# watCalSchematic.net
KiCad netlist of a schematic drawn in EAGLE
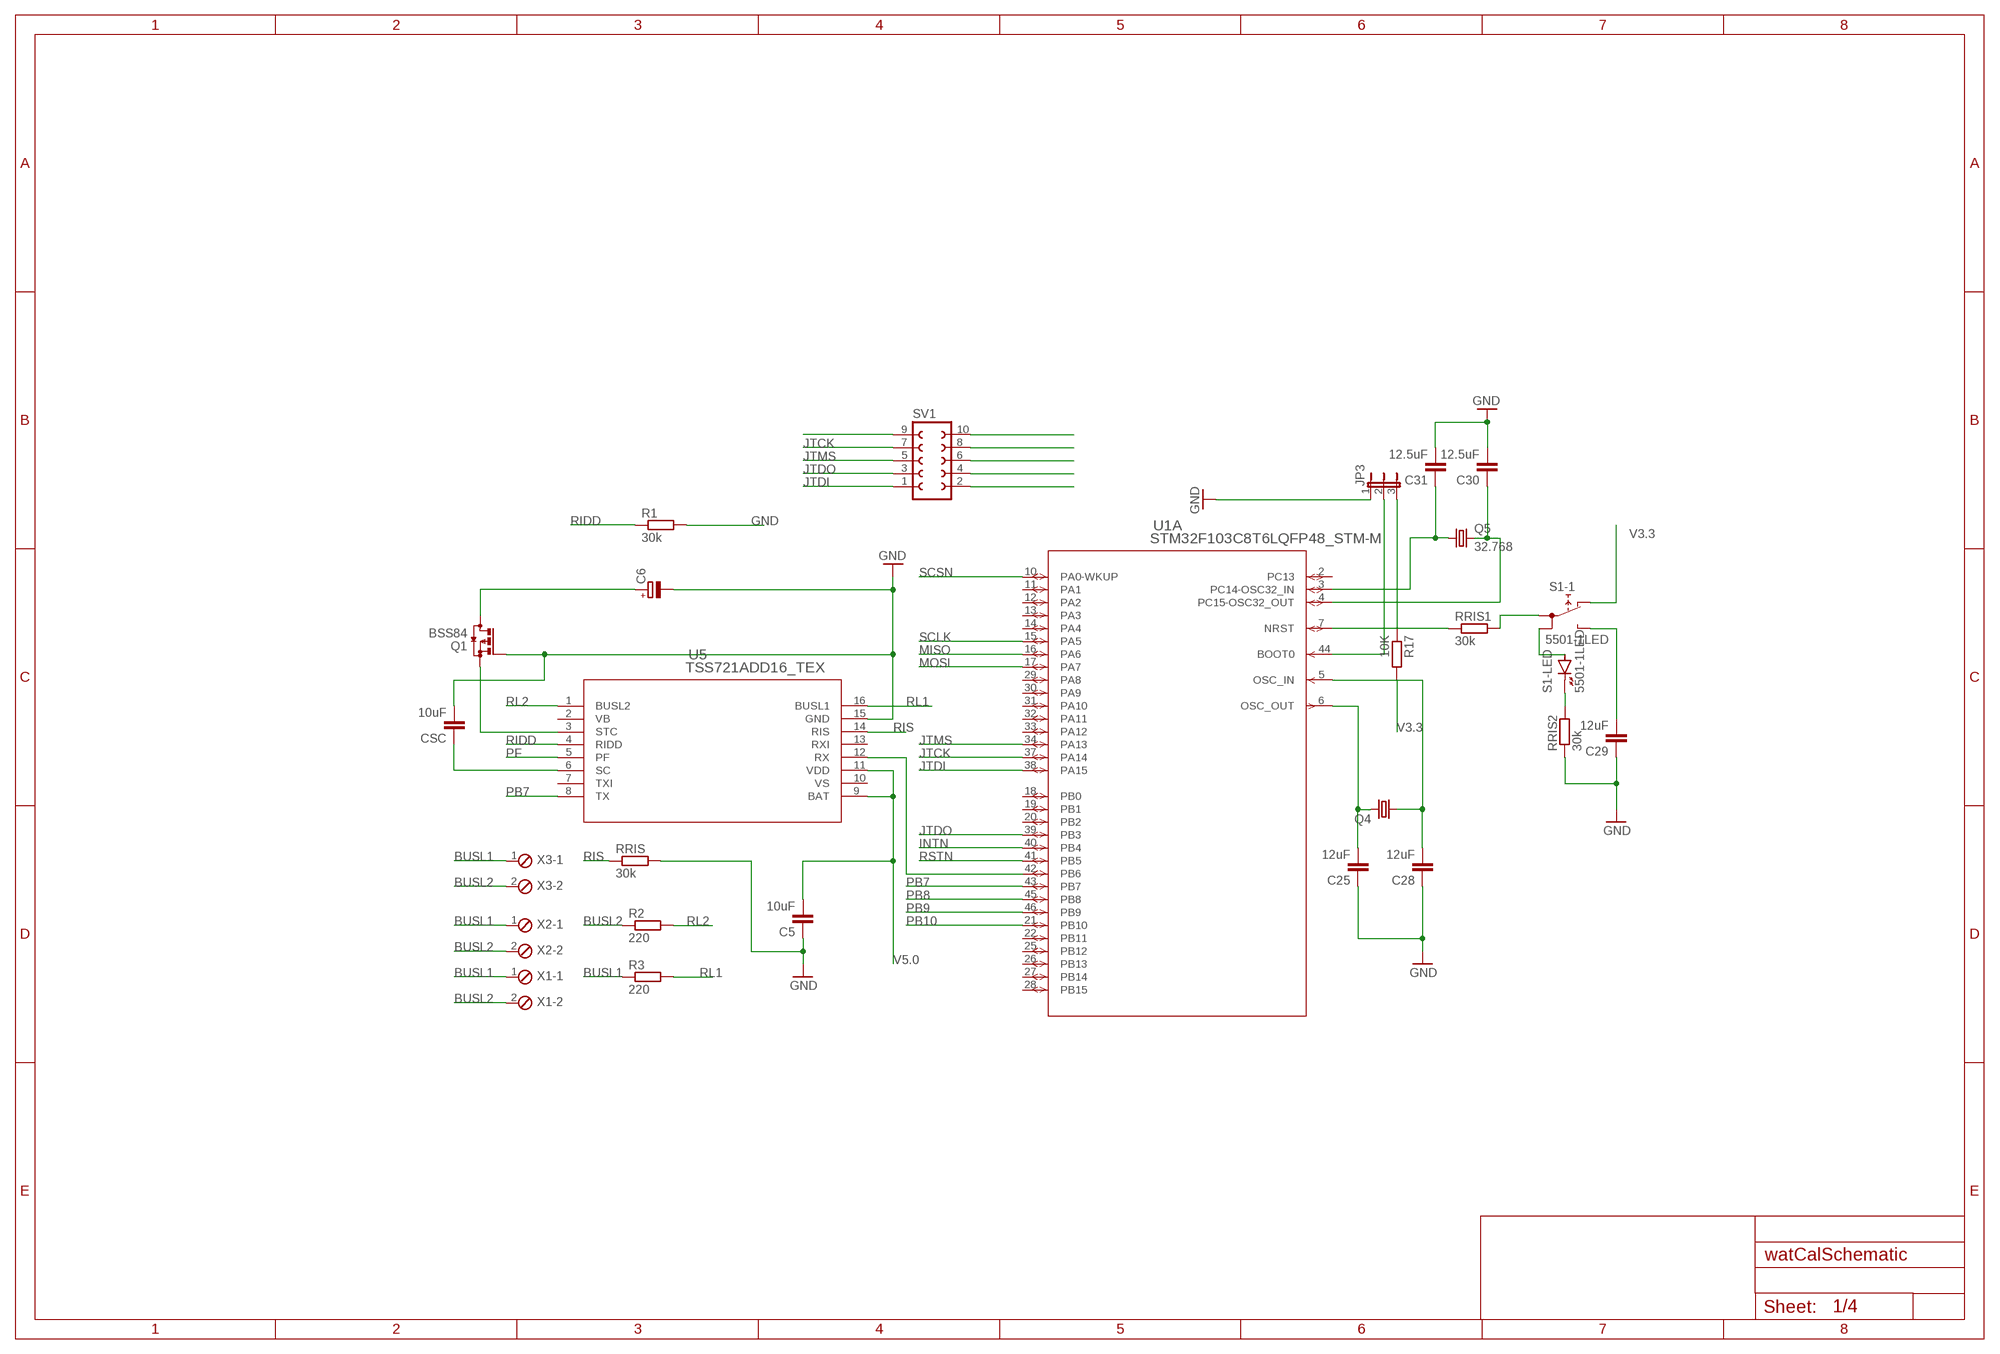
[diagram p0: schematic, sheet 1]
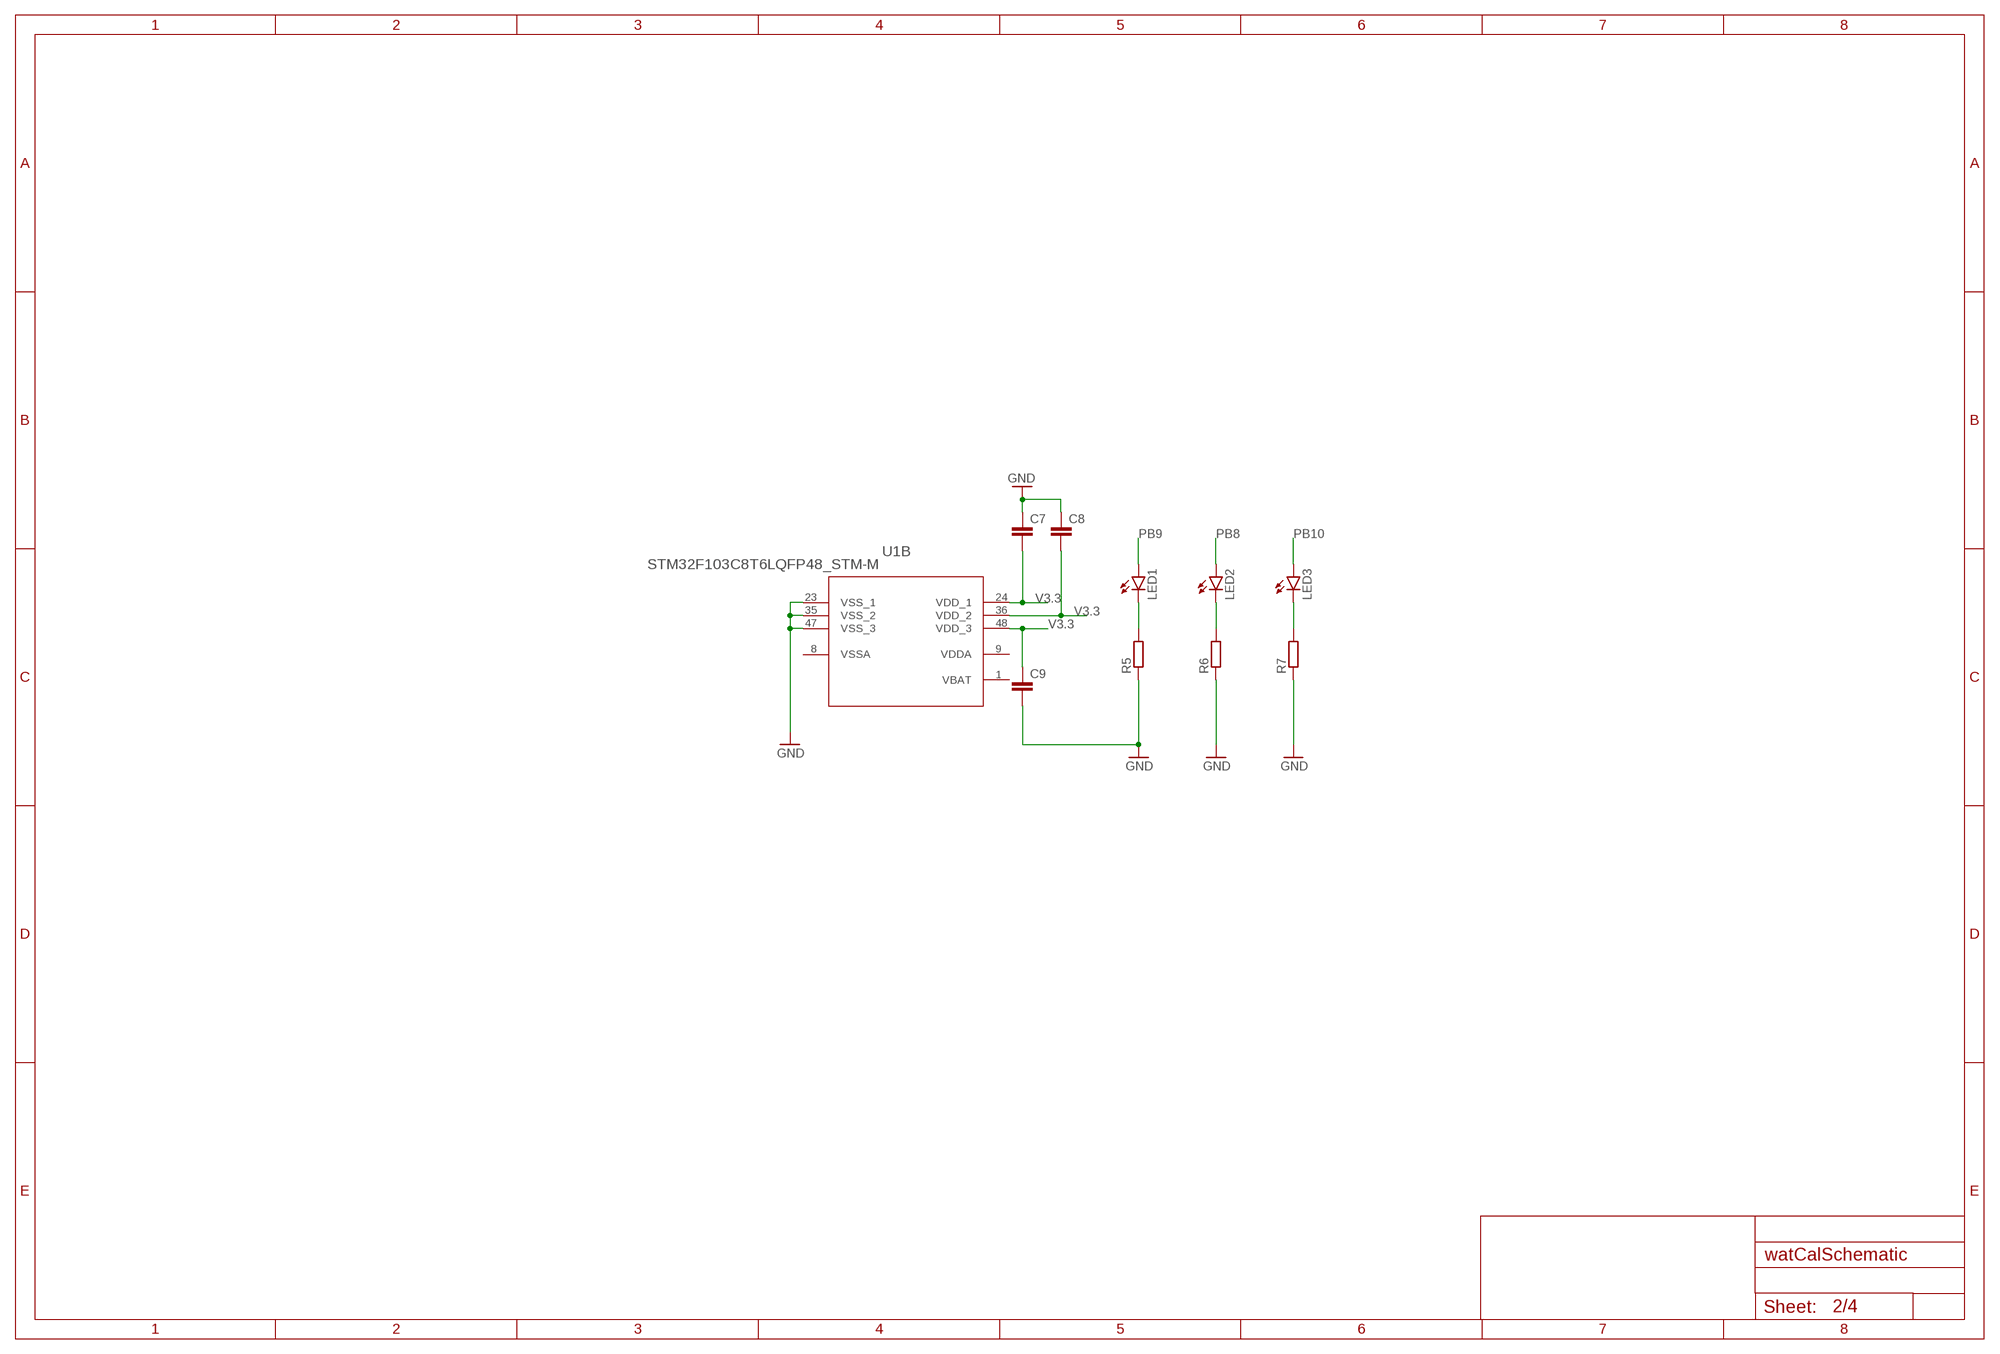
[diagram p1: schematic, sheet 2]
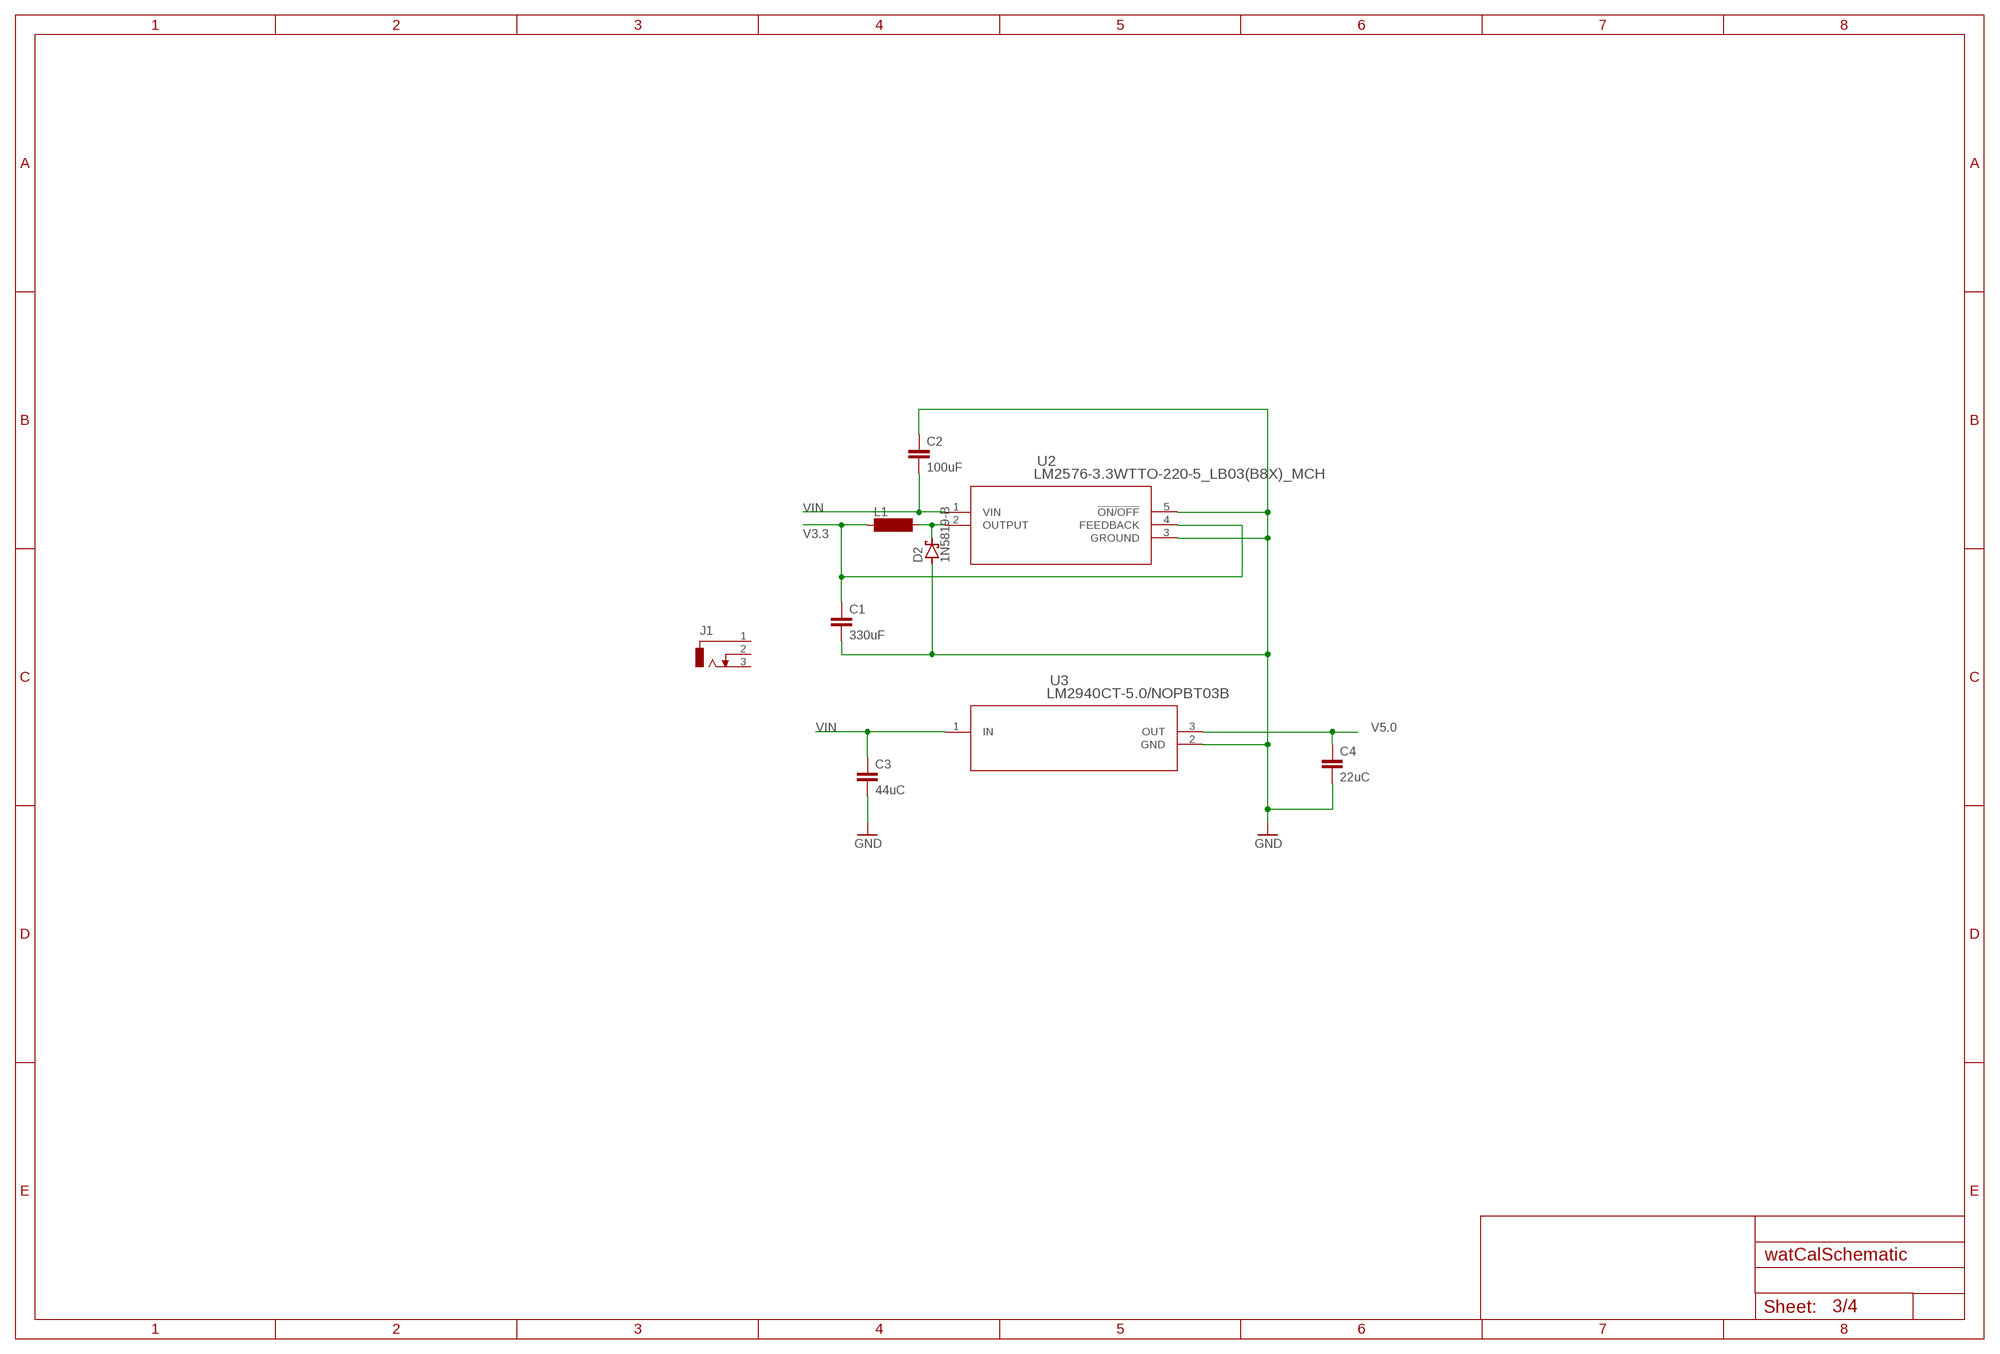
[diagram p2: schematic, sheet 3]
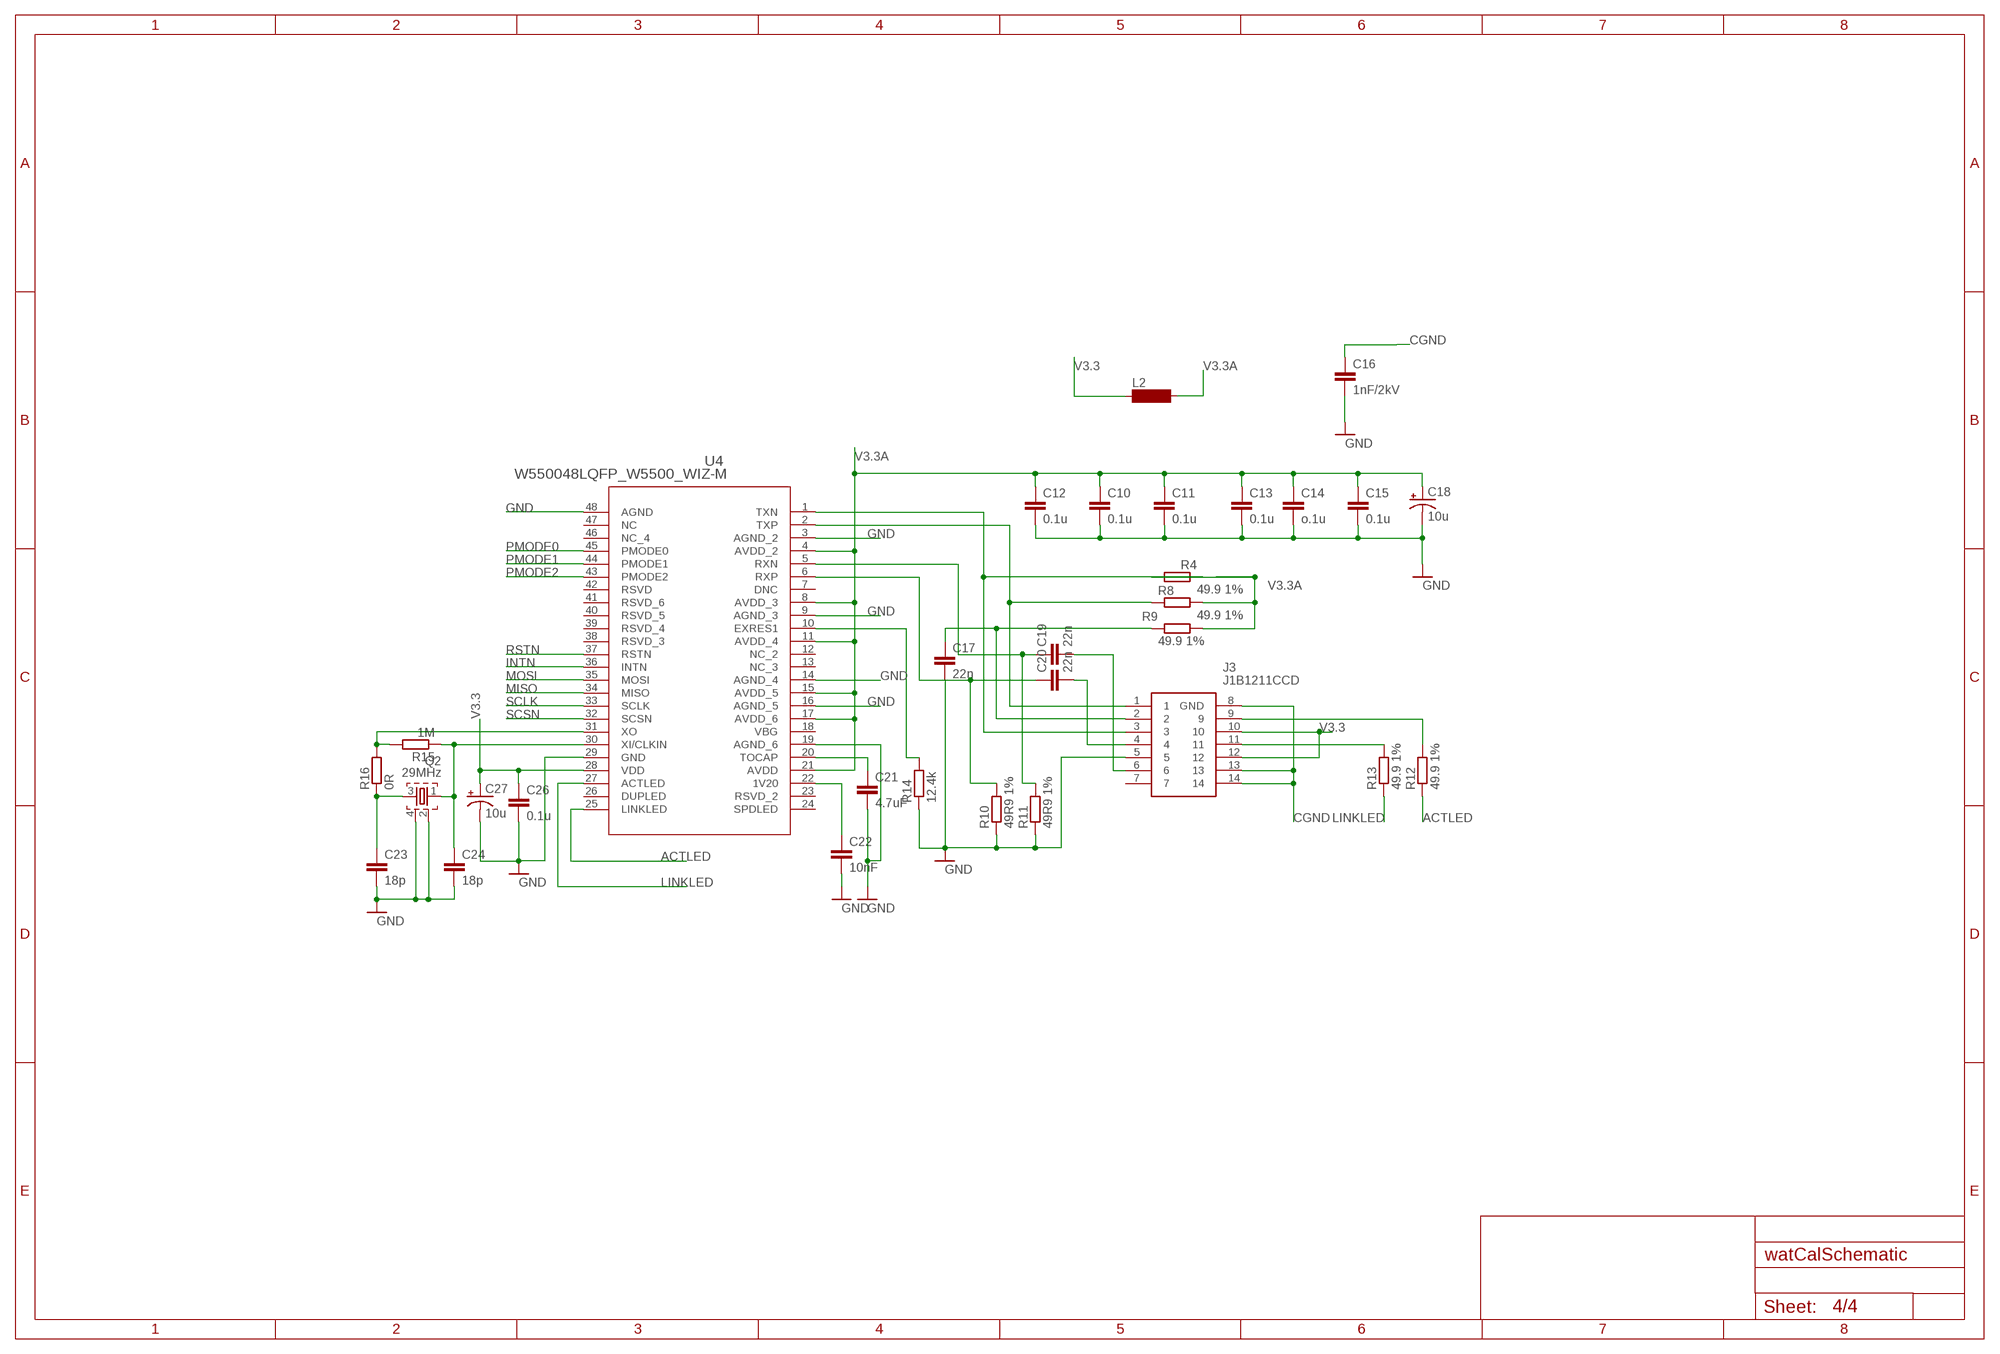
[diagram p3: schematic, sheet 4]

(export (version "E")
  (design (tool "Eeschema 10.0.6"))
  (components
    (comp (ref "C1")
      (value "330uF")
      (footprint "eagle-import:C2.5-2")
      (libsource (lib "eagle-import") (part "C2.5/2"))
    )
    (comp (ref "C2")
      (value "100uF")
      (footprint "eagle-import:C2.5-2")
      (libsource (lib "eagle-import") (part "C2.5/2"))
    )
    (comp (ref "C3")
      (value "44uC")
      (footprint "eagle-import:C2.5-3")
      (libsource (lib "eagle-import") (part "C2,5-3"))
    )
    (comp (ref "C4")
      (value "22uC")
      (footprint "eagle-import:C2.5-3")
      (libsource (lib "eagle-import") (part "C2,5-3"))
    )
    (comp (ref "D2")
      (value "1N5819-B")
      (footprint "eagle-import:DO41-7.6")
      (libsource (lib "eagle-import") (part "1N5819-B"))
    )
    (comp (ref "J1")
      (value "DCJ0303")
      (footprint "eagle-import:DCJ0303")
      (libsource (lib "eagle-import") (part "DCJ0303"))
    )
    (comp (ref "L1")
      (value "SD8")
      (footprint "eagle-import:SD8")
      (libsource (lib "eagle-import") (part "SD8"))
    )
    (comp (ref "U2")
      (value "LM2576-3.3WTTO-220-5_LB03(B8X)_MCH")
      (footprint "eagle-import:TO-220-5_LB03(B8X)_MCH")
      (fields
        (field (name "MANUFACTURER_PART_NUMBER") "LM2576-3.3WT")
        (field (name "COPYRIGHT") "Copyright (C) 2024 Ultra Librarian. All rights reserved.")
      )
      (libsource (lib "eagle-import") (part "LM2576-3.3WTTO-220-5_LB03(B8X)_MCH"))
    )
    (comp (ref "U3")
      (value "LM2940CT-5.0/NOPBT03B")
      (footprint "eagle-import:T03B")
      (fields
        (field (name "MANUFACTURER_PART_NUMBER") "LM2940CT-5.0/NOPB")
        (field (name "COPYRIGHT") "Copyright (C) 2024 Ultra Librarian. All rights reserved.")
      )
      (libsource (lib "eagle-import") (part "LM2940CT-5.0/NOPBT03B"))
    )
    (comp (ref "C7")
      (value "C2.5/2")
      (footprint "eagle-import:C2.5-2")
      (libsource (lib "eagle-import") (part "C2.5/2"))
    )
    (comp (ref "C8")
      (value "C2.5/2")
      (footprint "eagle-import:C2.5-2")
      (libsource (lib "eagle-import") (part "C2.5/2"))
    )
    (comp (ref "C9")
      (value "C2.5/2")
      (footprint "eagle-import:C2.5-2")
      (libsource (lib "eagle-import") (part "C2.5/2"))
    )
    (comp (ref "LED1")
      (value "LED5MM")
      (footprint "eagle-import:LED5MM")
      (libsource (lib "eagle-import") (part "LED5MM"))
    )
    (comp (ref "LED2")
      (value "LED5MM")
      (footprint "eagle-import:LED5MM")
      (libsource (lib "eagle-import") (part "LED5MM"))
    )
    (comp (ref "LED3")
      (value "LED5MM")
      (footprint "eagle-import:LED5MM")
      (libsource (lib "eagle-import") (part "LED5MM"))
    )
    (comp (ref "R5")
      (value "R-EU_0207/10")
      (footprint "eagle-import:0207_10")
      (libsource (lib "eagle-import") (part "R-EU_0207/10"))
    )
    (comp (ref "R6")
      (value "R-EU_0207/10")
      (footprint "eagle-import:0207_10")
      (libsource (lib "eagle-import") (part "R-EU_0207/10"))
    )
    (comp (ref "R7")
      (value "R-EU_0207/10")
      (footprint "eagle-import:0207_10")
      (libsource (lib "eagle-import") (part "R-EU_0207/10"))
    )
    (comp (ref "U1")
      (value "STM32F103C8T6LQFP48_STM-M")
      (footprint "eagle-import:LQFP48_STM-M")
      (fields
        (field (name "MANUFACTURER_PART_NUMBER") "STM32F103C8T6")
        (field (name "COPYRIGHT") "Copyright (C) 2024 Ultra Librarian. All rights reserved.")
      )
      (libsource (lib "eagle-import") (part "STM32F103C8T6LQFP48_STM-M"))
    )
    (comp (ref "C5")
      (value "10uF")
      (footprint "eagle-import:C2.5-2")
      (libsource (lib "eagle-import") (part "C2.5/2"))
    )
    (comp (ref "C6")
      (value "CPOL-EUE2,5-6E")
      (footprint "eagle-import:E2,5-6E")
      (libsource (lib "eagle-import") (part "CPOL-EUE2,5-6E"))
    )
    (comp (ref "C25")
      (value "12uF")
      (footprint "eagle-import:C2.5-2")
      (libsource (lib "eagle-import") (part "C2.5/2"))
    )
    (comp (ref "C28")
      (value "12uF")
      (footprint "eagle-import:C2.5-2")
      (libsource (lib "eagle-import") (part "C2.5/2"))
    )
    (comp (ref "C29")
      (value "12uF")
      (footprint "eagle-import:C2.5-2")
      (libsource (lib "eagle-import") (part "C2.5/2"))
    )
    (comp (ref "C30")
      (value "12.5uF")
      (footprint "eagle-import:C2.5-2")
      (libsource (lib "eagle-import") (part "C2.5/2"))
    )
    (comp (ref "C31")
      (value "12.5uF")
      (footprint "eagle-import:C2.5-2")
      (libsource (lib "eagle-import") (part "C2.5/2"))
    )
    (comp (ref "CSC")
      (value "10uF")
      (footprint "eagle-import:C2.5-2")
      (libsource (lib "eagle-import") (part "C2.5/2"))
    )
    (comp (ref "JP3")
      (value "JP2E")
      (footprint "eagle-import:JP2")
      (libsource (lib "eagle-import") (part "JP2E"))
    )
    (comp (ref "Q1")
      (value "BSS84")
      (footprint "eagle-import:SOT23")
      (libsource (lib "eagle-import") (part "BSS84"))
    )
    (comp (ref "Q4")
      (value "CRYSTALHC49S")
      (footprint "eagle-import:HC49_S")
      (libsource (lib "eagle-import") (part "CRYSTALHC49S"))
    )
    (comp (ref "Q5")
      (value "32.768")
      (footprint "eagle-import:FC-12M")
      (libsource (lib "eagle-import") (part "FC-12M"))
    )
    (comp (ref "R1")
      (value "30k")
      (footprint "eagle-import:0207_10")
      (libsource (lib "eagle-import") (part "R-EU_0207/10"))
    )
    (comp (ref "R2")
      (value "220")
      (footprint "eagle-import:0207_10")
      (libsource (lib "eagle-import") (part "R-EU_0207/10"))
    )
    (comp (ref "R3")
      (value "220")
      (footprint "eagle-import:0207_10")
      (libsource (lib "eagle-import") (part "R-EU_0207/10"))
    )
    (comp (ref "R17")
      (value "10K")
      (footprint "eagle-import:0207_10")
      (libsource (lib "eagle-import") (part "R-EU_0207/10"))
    )
    (comp (ref "RRIS")
      (value "30k")
      (footprint "eagle-import:0207_10")
      (libsource (lib "eagle-import") (part "R-EU_0207/10"))
    )
    (comp (ref "RRIS1")
      (value "30k")
      (footprint "eagle-import:0207_10")
      (libsource (lib "eagle-import") (part "R-EU_0207/10"))
    )
    (comp (ref "RRIS2")
      (value "30k")
      (footprint "eagle-import:0207_10")
      (libsource (lib "eagle-import") (part "R-EU_0207/10"))
    )
    (comp (ref "S1")
      (value "5501-1LED")
      (footprint "eagle-import:5501-1LED")
      (libsource (lib "eagle-import") (part "55?-1LED01"))
    )
    (comp (ref "SV1")
      (value "FE05-2")
      (footprint "eagle-import:FE05-2")
      (libsource (lib "eagle-import") (part "FE05-2"))
    )
    (comp (ref "U5")
      (value "TSS721ADD16_TEX")
      (footprint "eagle-import:D16_TEX")
      (fields
        (field (name "MANUFACTURER_PART_NUMBER") "TSS721AD")
        (field (name "COPYRIGHT") "Copyright (C) 2024 Ultra Librarian. All rights reserved.")
      )
      (libsource (lib "eagle-import") (part "TSS721ADD16_TEX"))
    )
    (comp (ref "X1")
      (value "MPT2")
      (footprint "eagle-import:2POL254")
      (libsource (lib "eagle-import") (part "MPT2"))
    )
    (comp (ref "X2")
      (value "MPT2")
      (footprint "eagle-import:2POL254")
      (libsource (lib "eagle-import") (part "MPT2"))
    )
    (comp (ref "X3")
      (value "MPT2")
      (footprint "eagle-import:2POL254")
      (libsource (lib "eagle-import") (part "MPT2"))
    )
    (comp (ref "C10")
      (value "0.1u")
      (footprint "eagle-import:C2.5-2")
      (libsource (lib "eagle-import") (part "C2.5/2"))
    )
    (comp (ref "C11")
      (value "0.1u")
      (footprint "eagle-import:C2.5-2")
      (libsource (lib "eagle-import") (part "C2.5/2"))
    )
    (comp (ref "C12")
      (value "0.1u")
      (footprint "eagle-import:C2.5-2")
      (libsource (lib "eagle-import") (part "C2.5/2"))
    )
    (comp (ref "C13")
      (value "0.1u")
      (footprint "eagle-import:C2.5-2")
      (libsource (lib "eagle-import") (part "C2.5/2"))
    )
    (comp (ref "C14")
      (value "o.1u")
      (footprint "eagle-import:C2.5-2")
      (libsource (lib "eagle-import") (part "C2.5/2"))
    )
    (comp (ref "C15")
      (value "0.1u")
      (footprint "eagle-import:C2.5-2")
      (libsource (lib "eagle-import") (part "C2.5/2"))
    )
    (comp (ref "C16")
      (value "1nF/2kV")
      (footprint "eagle-import:C2.5-2")
      (libsource (lib "eagle-import") (part "C2.5/2"))
    )
    (comp (ref "C17")
      (value "22n")
      (footprint "eagle-import:C2.5-2")
      (libsource (lib "eagle-import") (part "C2.5/2"))
    )
    (comp (ref "C18")
      (value "10u")
      (footprint "eagle-import:E2,5-6")
      (libsource (lib "eagle-import") (part "CPOL-USE2.5-6"))
    )
    (comp (ref "C19")
      (value "22n")
      (footprint "eagle-import:C2.5-2")
      (libsource (lib "eagle-import") (part "C2.5/2"))
    )
    (comp (ref "C20")
      (value "22n")
      (footprint "eagle-import:C2.5-2")
      (libsource (lib "eagle-import") (part "C2.5/2"))
    )
    (comp (ref "C21")
      (value "4.7uF")
      (footprint "eagle-import:C2.5-2")
      (libsource (lib "eagle-import") (part "C2.5/2"))
    )
    (comp (ref "C22")
      (value "10nF")
      (footprint "eagle-import:C2.5-2")
      (libsource (lib "eagle-import") (part "C2.5/2"))
    )
    (comp (ref "C23")
      (value "18p")
      (footprint "eagle-import:C2.5-2")
      (libsource (lib "eagle-import") (part "C2.5/2"))
    )
    (comp (ref "C24")
      (value "18p")
      (footprint "eagle-import:C2.5-2")
      (libsource (lib "eagle-import") (part "C2.5/2"))
    )
    (comp (ref "C26")
      (value "0.1u")
      (footprint "eagle-import:C2.5-2")
      (libsource (lib "eagle-import") (part "C2.5/2"))
    )
    (comp (ref "C27")
      (value "10u")
      (footprint "eagle-import:E2,5-6")
      (libsource (lib "eagle-import") (part "CPOL-USE2.5-6"))
    )
    (comp (ref "J3")
      (value "J1B1211CCD")
      (footprint "eagle-import:J1B1211CCD")
      (libsource (lib "eagle-import") (part "J1B1211CCD"))
    )
    (comp (ref "L2")
      (value "SD8")
      (footprint "eagle-import:SD8")
      (libsource (lib "eagle-import") (part "SD8"))
    )
    (comp (ref "Q2")
      (value "29MHz")
      (footprint "eagle-import:FA-20H")
      (libsource (lib "eagle-import") (part "FA-20H"))
    )
    (comp (ref "R4")
      (value "49.9 1%")
      (footprint "eagle-import:0207_10")
      (libsource (lib "eagle-import") (part "R-EU_0207/10"))
    )
    (comp (ref "R8")
      (value "49.9 1%")
      (footprint "eagle-import:0207_10")
      (libsource (lib "eagle-import") (part "R-EU_0207/10"))
    )
    (comp (ref "R9")
      (value "49.9 1%")
      (footprint "eagle-import:0207_10")
      (libsource (lib "eagle-import") (part "R-EU_0207/10"))
    )
    (comp (ref "R10")
      (value "49R9 1%")
      (footprint "eagle-import:0207_10")
      (libsource (lib "eagle-import") (part "R-EU_0207/10"))
    )
    (comp (ref "R11")
      (value "49R9 1%")
      (footprint "eagle-import:0207_10")
      (libsource (lib "eagle-import") (part "R-EU_0207/10"))
    )
    (comp (ref "R12")
      (value "49.9 1%")
      (footprint "eagle-import:0207_10")
      (libsource (lib "eagle-import") (part "R-EU_0207/10"))
    )
    (comp (ref "R13")
      (value "49.9 1%")
      (footprint "eagle-import:0207_10")
      (libsource (lib "eagle-import") (part "R-EU_0207/10"))
    )
    (comp (ref "R14")
      (value "12.4k")
      (footprint "eagle-import:0207_10")
      (libsource (lib "eagle-import") (part "R-EU_0207/10"))
    )
    (comp (ref "R15")
      (value "1M")
      (footprint "eagle-import:0207_10")
      (libsource (lib "eagle-import") (part "R-EU_0207/10"))
    )
    (comp (ref "R16")
      (value "0R")
      (footprint "eagle-import:0207_10")
      (libsource (lib "eagle-import") (part "R-EU_0207/10"))
    )
    (comp (ref "U4")
      (value "W550048LQFP_W5500_WIZ-M")
      (footprint "eagle-import:48LQFP_W5500_WIZ-M")
      (fields
        (field (name "MANUFACTURER_PART_NUMBER") "W5500")
        (field (name "COPYRIGHT") "Copyright (C) 2024 Ultra Librarian. All rights reserved.")
      )
      (libsource (lib "eagle-import") (part "W550048LQFP_W5500_WIZ-M"))
    )
  )
  (nets
    (net (code "1") (name "ACTLED") (class "Default")
      (node (ref "R12") (pin "1") (pinfunction "1_1") (pintype "passive"))
      (node (ref "U4") (pin "25") (pinfunction "LINKLED_25") (pintype "passive"))
    )
    (net (code "2") (name "BUSL1") (class "Default")
      (node (ref "R3") (pin "1") (pinfunction "1_1") (pintype "passive"))
      (node (ref "X1") (pin "1") (pinfunction "1_1") (pintype "passive"))
      (node (ref "X2") (pin "1") (pinfunction "1_1") (pintype "passive"))
      (node (ref "X3") (pin "1") (pinfunction "1_1") (pintype "passive"))
    )
    (net (code "3") (name "BUSL2") (class "Default")
      (node (ref "R2") (pin "1") (pinfunction "1_1") (pintype "passive"))
      (node (ref "X1") (pin "2") (pinfunction "1_2") (pintype "passive"))
      (node (ref "X2") (pin "2") (pinfunction "1_2") (pintype "passive"))
      (node (ref "X3") (pin "2") (pinfunction "1_2") (pintype "passive"))
    )
    (net (code "4") (name "CGND") (class "Default")
      (node (ref "C16") (pin "1") (pinfunction "1_1") (pintype "passive"))
      (node (ref "J3") (pin "13") (pinfunction "13_13") (pintype "bidirectional"))
      (node (ref "J3") (pin "14") (pinfunction "14_14") (pintype "bidirectional"))
      (node (ref "J3") (pin "8") (pinfunction "GND_8") (pintype "bidirectional"))
    )
    (net (code "5") (name "GND") (class "Default")
      (node (ref "C1") (pin "2") (pinfunction "2_2") (pintype "passive"))
      (node (ref "C10") (pin "2") (pinfunction "2_2") (pintype "passive"))
      (node (ref "C11") (pin "2") (pinfunction "2_2") (pintype "passive"))
      (node (ref "C12") (pin "2") (pinfunction "2_2") (pintype "passive"))
      (node (ref "C13") (pin "2") (pinfunction "2_2") (pintype "passive"))
      (node (ref "C14") (pin "2") (pinfunction "2_2") (pintype "passive"))
      (node (ref "C15") (pin "2") (pinfunction "2_2") (pintype "passive"))
      (node (ref "C16") (pin "2") (pinfunction "2_2") (pintype "passive"))
      (node (ref "C17") (pin "2") (pinfunction "2_2") (pintype "passive"))
      (node (ref "C18") (pin "-") (pinfunction "-_-") (pintype "passive"))
      (node (ref "C2") (pin "1") (pinfunction "1_1") (pintype "passive"))
      (node (ref "C21") (pin "2") (pinfunction "2_2") (pintype "passive"))
      (node (ref "C22") (pin "2") (pinfunction "2_2") (pintype "passive"))
      (node (ref "C23") (pin "2") (pinfunction "2_2") (pintype "passive"))
      (node (ref "C24") (pin "2") (pinfunction "2_2") (pintype "passive"))
      (node (ref "C25") (pin "1") (pinfunction "1_1") (pintype "passive"))
      (node (ref "C26") (pin "2") (pinfunction "2_2") (pintype "passive"))
      (node (ref "C27") (pin "-") (pinfunction "-_-") (pintype "passive"))
      (node (ref "C28") (pin "1") (pinfunction "1_1") (pintype "passive"))
      (node (ref "C29") (pin "1") (pinfunction "1_1") (pintype "passive"))
      (node (ref "C3") (pin "2") (pinfunction "2_2") (pintype "passive"))
      (node (ref "C30") (pin "2") (pinfunction "2_2") (pintype "passive"))
      (node (ref "C31") (pin "2") (pinfunction "2_2") (pintype "passive"))
      (node (ref "C4") (pin "2") (pinfunction "2_2") (pintype "passive"))
      (node (ref "C5") (pin "1") (pinfunction "1_1") (pintype "passive"))
      (node (ref "C6") (pin "-") (pinfunction "-_-") (pintype "passive"))
      (node (ref "C7") (pin "1") (pinfunction "1_1") (pintype "passive"))
      (node (ref "C8") (pin "1") (pinfunction "1_1") (pintype "passive"))
      (node (ref "C9") (pin "2") (pinfunction "2_2") (pintype "passive"))
      (node (ref "CSC") (pin "2") (pinfunction "2_2") (pintype "passive"))
      (node (ref "D2") (pin "A") (pinfunction "A_A") (pintype "passive"))
      (node (ref "J3") (pin "5") (pinfunction "5_5") (pintype "bidirectional"))
      (node (ref "JP3") (pin "1") (pinfunction "1_1") (pintype "passive"))
      (node (ref "Q1") (pin "1") (pinfunction "G_1") (pintype "passive"))
      (node (ref "Q2") (pin "2") (pinfunction "2_2") (pintype "passive"))
      (node (ref "Q2") (pin "4") (pinfunction "4_4") (pintype "passive"))
      (node (ref "R1") (pin "2") (pinfunction "2_2") (pintype "passive"))
      (node (ref "R10") (pin "1") (pinfunction "1_1") (pintype "passive"))
      (node (ref "R11") (pin "1") (pinfunction "1_1") (pintype "passive"))
      (node (ref "R14") (pin "1") (pinfunction "1_1") (pintype "passive"))
      (node (ref "R5") (pin "1") (pinfunction "1_1") (pintype "passive"))
      (node (ref "R6") (pin "1") (pinfunction "1_1") (pintype "passive"))
      (node (ref "R7") (pin "1") (pinfunction "1_1") (pintype "passive"))
      (node (ref "RRIS") (pin "2") (pinfunction "2_2") (pintype "passive"))
      (node (ref "RRIS2") (pin "1") (pinfunction "1_1") (pintype "passive"))
      (node (ref "U1") (pin "23") (pinfunction "VSS_1_23") (pintype "power_in"))
      (node (ref "U1") (pin "35") (pinfunction "VSS_2_35") (pintype "power_in"))
      (node (ref "U1") (pin "47") (pinfunction "VSS_3_47") (pintype "power_in"))
      (node (ref "U2") (pin "3") (pinfunction "GROUND_3") (pintype "passive"))
      (node (ref "U2") (pin "5") (pinfunction "~{ON/OFF}_5") (pintype "input"))
      (node (ref "U3") (pin "2") (pinfunction "GND_2") (pintype "passive"))
      (node (ref "U4") (pin "14") (pinfunction "AGND_4_14") (pintype "passive"))
      (node (ref "U4") (pin "16") (pinfunction "AGND_5_16") (pintype "passive"))
      (node (ref "U4") (pin "19") (pinfunction "AGND_6_19") (pintype "passive"))
      (node (ref "U4") (pin "29") (pinfunction "GND_29") (pintype "passive"))
      (node (ref "U4") (pin "3") (pinfunction "AGND_2_3") (pintype "passive"))
      (node (ref "U4") (pin "48") (pinfunction "AGND_48") (pintype "passive"))
      (node (ref "U4") (pin "9") (pinfunction "AGND_3_9") (pintype "passive"))
      (node (ref "U5") (pin "15") (pinfunction "GND_15") (pintype "power_in"))
    )
    (net (code "6") (name "INTN") (class "Default")
      (node (ref "U1") (pin "40") (pinfunction "PB4_40") (pintype "bidirectional"))
      (node (ref "U4") (pin "36") (pinfunction "INTN_36") (pintype "passive"))
    )
    (net (code "7") (name "JTCK") (class "Default")
      (node (ref "SV1") (pin "7") (pinfunction "7_7") (pintype "passive"))
      (node (ref "U1") (pin "37") (pinfunction "PA14_37") (pintype "bidirectional"))
    )
    (net (code "8") (name "JTDI") (class "Default")
      (node (ref "SV1") (pin "1") (pinfunction "1_1") (pintype "passive"))
      (node (ref "U1") (pin "38") (pinfunction "PA15_38") (pintype "bidirectional"))
    )
    (net (code "9") (name "JTDO") (class "Default")
      (node (ref "SV1") (pin "3") (pinfunction "3_3") (pintype "passive"))
      (node (ref "U1") (pin "39") (pinfunction "PB3_39") (pintype "bidirectional"))
    )
    (net (code "10") (name "JTMS") (class "Default")
      (node (ref "SV1") (pin "5") (pinfunction "5_5") (pintype "passive"))
      (node (ref "U1") (pin "34") (pinfunction "PA13_34") (pintype "bidirectional"))
    )
    (net (code "11") (name "LINKLED") (class "Default")
      (node (ref "R13") (pin "1") (pinfunction "1_1") (pintype "passive"))
      (node (ref "U4") (pin "27") (pinfunction "ACTLED_27") (pintype "passive"))
    )
    (net (code "12") (name "MISO") (class "Default")
      (node (ref "U1") (pin "16") (pinfunction "PA6_16") (pintype "bidirectional"))
      (node (ref "U4") (pin "34") (pinfunction "MISO_34") (pintype "passive"))
    )
    (net (code "13") (name "MOSI") (class "Default")
      (node (ref "U1") (pin "17") (pinfunction "PA7_17") (pintype "bidirectional"))
      (node (ref "U4") (pin "35") (pinfunction "MOSI_35") (pintype "passive"))
    )
    (net (code "14") (name "Net-(C17-Pad1)") (class "Default")
      (node (ref "C17") (pin "1") (pinfunction "1_1") (pintype "passive"))
      (node (ref "J3") (pin "2") (pinfunction "2_2") (pintype "bidirectional"))
      (node (ref "R9") (pin "1") (pinfunction "1_1") (pintype "passive"))
    )
    (net (code "15") (name "Net-(C19-Pad2)") (class "Default")
      (node (ref "C19") (pin "2") (pinfunction "2_2") (pintype "passive"))
      (node (ref "J3") (pin "6") (pinfunction "6_6") (pintype "bidirectional"))
    )
    (net (code "16") (name "Net-(C20-Pad2)") (class "Default")
      (node (ref "C20") (pin "2") (pinfunction "2_2") (pintype "passive"))
      (node (ref "J3") (pin "4") (pinfunction "4_4") (pintype "bidirectional"))
    )
    (net (code "17") (name "Net-(C23-Pad1)") (class "Default")
      (node (ref "C23") (pin "1") (pinfunction "1_1") (pintype "passive"))
      (node (ref "Q2") (pin "3") (pinfunction "3_3") (pintype "passive"))
      (node (ref "R16") (pin "1") (pinfunction "1_1") (pintype "passive"))
    )
    (net (code "18") (name "Net-(C29-Pad2)") (class "Default")
      (node (ref "C29") (pin "2") (pinfunction "2_2") (pintype "passive"))
      (node (ref "S1") (pin "NO") (pinfunction "NO_NO") (pintype "passive"))
    )
    (net (code "19") (name "Net-(J3-Pad9)") (class "Default")
      (node (ref "J3") (pin "9") (pinfunction "9_9") (pintype "bidirectional"))
      (node (ref "R12") (pin "2") (pinfunction "2_2") (pintype "passive"))
    )
    (net (code "20") (name "Net-(J3-Pad11)") (class "Default")
      (node (ref "J3") (pin "11") (pinfunction "11_11") (pintype "bidirectional"))
      (node (ref "R13") (pin "2") (pinfunction "2_2") (pintype "passive"))
    )
    (net (code "21") (name "Net-(JP3-Pad3)") (class "Default")
      (node (ref "JP3") (pin "3") (pinfunction "3_3") (pintype "passive"))
      (node (ref "R17") (pin "1") (pinfunction "1_1") (pintype "passive"))
    )
    (net (code "22") (name "Net-(LED1-C)") (class "Default")
      (node (ref "LED1") (pin "K") (pinfunction "C_K") (pintype "passive"))
      (node (ref "R5") (pin "2") (pinfunction "2_2") (pintype "passive"))
    )
    (net (code "23") (name "Net-(LED2-C)") (class "Default")
      (node (ref "LED2") (pin "K") (pinfunction "C_K") (pintype "passive"))
      (node (ref "R6") (pin "2") (pinfunction "2_2") (pintype "passive"))
    )
    (net (code "24") (name "Net-(LED3-C)") (class "Default")
      (node (ref "LED3") (pin "K") (pinfunction "C_K") (pintype "passive"))
      (node (ref "R7") (pin "2") (pinfunction "2_2") (pintype "passive"))
    )
    (net (code "25") (name "Net-(Q1-D)") (class "Default")
      (node (ref "C6") (pin "+") (pinfunction "+_+") (pintype "passive"))
      (node (ref "Q1") (pin "3") (pinfunction "D_3") (pintype "passive"))
    )
    (net (code "26") (name "Net-(Q1-S)") (class "Default")
      (node (ref "Q1") (pin "2") (pinfunction "S_2") (pintype "passive"))
      (node (ref "U5") (pin "3") (pinfunction "STC_3") (pintype "passive"))
    )
    (net (code "27") (name "Net-(RRIS1-Pad2)") (class "Default")
      (node (ref "RRIS1") (pin "2") (pinfunction "2_2") (pintype "passive"))
      (node (ref "S1") (pin "1A") (pinfunction "1A_1A") (pintype "passive"))
    )
    (net (code "28") (name "Net-(S1B-A)") (class "Default")
      (node (ref "S1") (pin "+") (pinfunction "A_+") (pintype "passive"))
      (node (ref "S1") (pin "1B") (pinfunction "1B_1B") (pintype "passive"))
    )
    (net (code "29") (name "Net-(S1B-K)") (class "Default")
      (node (ref "RRIS2") (pin "2") (pinfunction "2_2") (pintype "passive"))
      (node (ref "S1") (pin "-") (pinfunction "K_-") (pintype "passive"))
    )
    (net (code "30") (name "Net-(U1A-BOOT0)") (class "Default")
      (node (ref "JP3") (pin "2") (pinfunction "2_2") (pintype "passive"))
      (node (ref "U1") (pin "44") (pinfunction "BOOT0_44") (pintype "input"))
    )
    (net (code "31") (name "Net-(U1A-NRST)") (class "Default")
      (node (ref "RRIS1") (pin "1") (pinfunction "1_1") (pintype "passive"))
      (node (ref "U1") (pin "7") (pinfunction "NRST_7") (pintype "bidirectional"))
    )
    (net (code "32") (name "Net-(U1A-OSC_IN)") (class "Default")
      (node (ref "C28") (pin "2") (pinfunction "2_2") (pintype "passive"))
      (node (ref "Q4") (pin "1") (pinfunction "1_1") (pintype "passive"))
      (node (ref "U1") (pin "5") (pinfunction "OSC_IN_5") (pintype "input"))
    )
    (net (code "33") (name "Net-(U1A-OSC_OUT)") (class "Default")
      (node (ref "C25") (pin "2") (pinfunction "2_2") (pintype "passive"))
      (node (ref "Q4") (pin "2") (pinfunction "2_2") (pintype "passive"))
      (node (ref "U1") (pin "6") (pinfunction "OSC_OUT_6") (pintype "output"))
    )
    (net (code "34") (name "Net-(U1A-PB6)") (class "Default")
      (node (ref "U1") (pin "42") (pinfunction "PB6_42") (pintype "bidirectional"))
      (node (ref "U5") (pin "12") (pinfunction "RX_12") (pintype "input"))
    )
    (net (code "35") (name "Net-(U1A-PC14-OSC32_IN)") (class "Default")
      (node (ref "C31") (pin "1") (pinfunction "1_1") (pintype "passive"))
      (node (ref "Q5") (pin "1") (pinfunction "1_1") (pintype "passive"))
      (node (ref "U1") (pin "3") (pinfunction "PC14-OSC32_IN_3") (pintype "bidirectional"))
    )
    (net (code "36") (name "Net-(U1A-PC15-OSC32_OUT)") (class "Default")
      (node (ref "C30") (pin "1") (pinfunction "1_1") (pintype "passive"))
      (node (ref "Q5") (pin "2") (pinfunction "2_2") (pintype "passive"))
      (node (ref "U1") (pin "4") (pinfunction "PC15-OSC32_OUT_4") (pintype "bidirectional"))
    )
    (net (code "37") (name "Net-(U2-OUTPUT)") (class "Default")
      (node (ref "D2") (pin "C") (pinfunction "C_C") (pintype "passive"))
      (node (ref "L1") (pin "2") (pinfunction "2_2") (pintype "passive"))
      (node (ref "U2") (pin "2") (pinfunction "OUTPUT_2") (pintype "output"))
    )
    (net (code "38") (name "Net-(U4-1V20)") (class "Default")
      (node (ref "C22") (pin "1") (pinfunction "1_1") (pintype "passive"))
      (node (ref "U4") (pin "22") (pinfunction "1V20_22") (pintype "passive"))
    )
    (net (code "39") (name "Net-(U4-EXRES1)") (class "Default")
      (node (ref "R14") (pin "2") (pinfunction "2_2") (pintype "passive"))
      (node (ref "U4") (pin "10") (pinfunction "EXRES1_10") (pintype "passive"))
    )
    (net (code "40") (name "Net-(U4-RXN)") (class "Default")
      (node (ref "C19") (pin "1") (pinfunction "1_1") (pintype "passive"))
      (node (ref "R11") (pin "2") (pinfunction "2_2") (pintype "passive"))
      (node (ref "U4") (pin "5") (pinfunction "RXN_5") (pintype "passive"))
    )
    (net (code "41") (name "Net-(U4-RXP)") (class "Default")
      (node (ref "C20") (pin "1") (pinfunction "1_1") (pintype "passive"))
      (node (ref "R10") (pin "2") (pinfunction "2_2") (pintype "passive"))
      (node (ref "U4") (pin "6") (pinfunction "RXP_6") (pintype "passive"))
    )
    (net (code "42") (name "Net-(U4-TOCAP)") (class "Default")
      (node (ref "C21") (pin "1") (pinfunction "1_1") (pintype "passive"))
      (node (ref "U4") (pin "20") (pinfunction "TOCAP_20") (pintype "passive"))
    )
    (net (code "43") (name "Net-(U4-TXN)") (class "Default")
      (node (ref "J3") (pin "3") (pinfunction "3_3") (pintype "bidirectional"))
      (node (ref "R4") (pin "1") (pinfunction "1_1") (pintype "passive"))
      (node (ref "U4") (pin "1") (pinfunction "TXN_1") (pintype "passive"))
    )
    (net (code "44") (name "Net-(U4-TXP)") (class "Default")
      (node (ref "J3") (pin "1") (pinfunction "1_1") (pintype "bidirectional"))
      (node (ref "R8") (pin "1") (pinfunction "1_1") (pintype "passive"))
      (node (ref "U4") (pin "2") (pinfunction "TXP_2") (pintype "passive"))
    )
    (net (code "45") (name "Net-(U4-XI{slash}CLKIN)") (class "Default")
      (node (ref "C24") (pin "1") (pinfunction "1_1") (pintype "passive"))
      (node (ref "Q2") (pin "1") (pinfunction "1_1") (pintype "passive"))
      (node (ref "R15") (pin "1") (pinfunction "1_1") (pintype "passive"))
      (node (ref "U4") (pin "30") (pinfunction "XI/CLKIN_30") (pintype "passive"))
    )
    (net (code "46") (name "Net-(U5-SC)") (class "Default")
      (node (ref "CSC") (pin "1") (pinfunction "1_1") (pintype "passive"))
      (node (ref "U5") (pin "6") (pinfunction "SC_6") (pintype "passive"))
    )
    (net (code "47") (name "PB7") (class "Default")
      (node (ref "U1") (pin "43") (pinfunction "PB7_43") (pintype "bidirectional"))
      (node (ref "U5") (pin "8") (pinfunction "TX_8") (pintype "output"))
    )
    (net (code "48") (name "PB8") (class "Default")
      (node (ref "LED2") (pin "A") (pinfunction "A_A") (pintype "passive"))
      (node (ref "U1") (pin "45") (pinfunction "PB8_45") (pintype "bidirectional"))
    )
    (net (code "49") (name "PB9") (class "Default")
      (node (ref "LED1") (pin "A") (pinfunction "A_A") (pintype "passive"))
      (node (ref "U1") (pin "46") (pinfunction "PB9_46") (pintype "bidirectional"))
    )
    (net (code "50") (name "PB10") (class "Default")
      (node (ref "LED3") (pin "A") (pinfunction "A_A") (pintype "passive"))
      (node (ref "U1") (pin "21") (pinfunction "PB10_21") (pintype "bidirectional"))
    )
    (net (code "51") (name "PF") (class "Default")
      (node (ref "U5") (pin "5") (pinfunction "PF_5") (pintype "output"))
    )
    (net (code "52") (name "PMODE0") (class "Default")
      (node (ref "U4") (pin "45") (pinfunction "PMODE0_45") (pintype "bidirectional"))
    )
    (net (code "53") (name "PMODE1") (class "Default")
      (node (ref "U4") (pin "44") (pinfunction "PMODE1_44") (pintype "bidirectional"))
    )
    (net (code "54") (name "PMODE2") (class "Default")
      (node (ref "U4") (pin "43") (pinfunction "PMODE2_43") (pintype "bidirectional"))
    )
    (net (code "55") (name "RIDD") (class "Default")
      (node (ref "R1") (pin "1") (pinfunction "1_1") (pintype "passive"))
      (node (ref "U5") (pin "4") (pinfunction "RIDD_4") (pintype "input"))
    )
    (net (code "56") (name "RIS") (class "Default")
      (node (ref "RRIS") (pin "1") (pinfunction "1_1") (pintype "passive"))
      (node (ref "U5") (pin "14") (pinfunction "RIS_14") (pintype "input"))
    )
    (net (code "57") (name "RL1") (class "Default")
      (node (ref "R3") (pin "2") (pinfunction "2_2") (pintype "passive"))
      (node (ref "U5") (pin "16") (pinfunction "BUSL1_16") (pintype "passive"))
    )
    (net (code "58") (name "RL2") (class "Default")
      (node (ref "R2") (pin "2") (pinfunction "2_2") (pintype "passive"))
      (node (ref "U5") (pin "1") (pinfunction "BUSL2_1") (pintype "passive"))
    )
    (net (code "59") (name "RSTN") (class "Default")
      (node (ref "U1") (pin "41") (pinfunction "PB5_41") (pintype "bidirectional"))
      (node (ref "U4") (pin "37") (pinfunction "RSTN_37") (pintype "passive"))
    )
    (net (code "60") (name "SCLK") (class "Default")
      (node (ref "U1") (pin "15") (pinfunction "PA5_15") (pintype "bidirectional"))
      (node (ref "U4") (pin "33") (pinfunction "SCLK_33") (pintype "passive"))
    )
    (net (code "61") (name "SCSN") (class "Default")
      (node (ref "R15") (pin "2") (pinfunction "2_2") (pintype "passive"))
      (node (ref "R16") (pin "2") (pinfunction "2_2") (pintype "passive"))
      (node (ref "U1") (pin "10") (pinfunction "PA0-WKUP_10") (pintype "bidirectional"))
      (node (ref "U4") (pin "31") (pinfunction "XO_31") (pintype "passive"))
    )
    (net (code "62") (name "V3.3") (class "Default")
      (node (ref "C1") (pin "1") (pinfunction "1_1") (pintype "passive"))
      (node (ref "C26") (pin "1") (pinfunction "1_1") (pintype "passive"))
      (node (ref "C27") (pin "+") (pinfunction "+_+") (pintype "passive"))
      (node (ref "C7") (pin "2") (pinfunction "2_2") (pintype "passive"))
      (node (ref "C8") (pin "2") (pinfunction "2_2") (pintype "passive"))
      (node (ref "C9") (pin "1") (pinfunction "1_1") (pintype "passive"))
      (node (ref "J3") (pin "10") (pinfunction "10_10") (pintype "bidirectional"))
      (node (ref "J3") (pin "12") (pinfunction "12_12") (pintype "bidirectional"))
      (node (ref "L1") (pin "1") (pinfunction "1_1") (pintype "passive"))
      (node (ref "L2") (pin "1") (pinfunction "1_1") (pintype "passive"))
      (node (ref "R17") (pin "2") (pinfunction "2_2") (pintype "passive"))
      (node (ref "S1") (pin "NC") (pinfunction "NC_NC") (pintype "passive"))
      (node (ref "U1") (pin "24") (pinfunction "VDD_1_24") (pintype "power_in"))
      (node (ref "U1") (pin "36") (pinfunction "VDD_2_36") (pintype "power_in"))
      (node (ref "U1") (pin "48") (pinfunction "VDD_3_48") (pintype "power_in"))
      (node (ref "U2") (pin "4") (pinfunction "FEEDBACK_4") (pintype "output"))
      (node (ref "U4") (pin "28") (pinfunction "VDD_28") (pintype "power_in"))
    )
    (net (code "63") (name "V3.3A") (class "Default")
      (node (ref "C10") (pin "1") (pinfunction "1_1") (pintype "passive"))
      (node (ref "C11") (pin "1") (pinfunction "1_1") (pintype "passive"))
      (node (ref "C12") (pin "1") (pinfunction "1_1") (pintype "passive"))
      (node (ref "C13") (pin "1") (pinfunction "1_1") (pintype "passive"))
      (node (ref "C14") (pin "1") (pinfunction "1_1") (pintype "passive"))
      (node (ref "C15") (pin "1") (pinfunction "1_1") (pintype "passive"))
      (node (ref "C18") (pin "+") (pinfunction "+_+") (pintype "passive"))
      (node (ref "L2") (pin "2") (pinfunction "2_2") (pintype "passive"))
      (node (ref "R4") (pin "2") (pinfunction "2_2") (pintype "passive"))
      (node (ref "R8") (pin "2") (pinfunction "2_2") (pintype "passive"))
      (node (ref "R9") (pin "2") (pinfunction "2_2") (pintype "passive"))
      (node (ref "U4") (pin "11") (pinfunction "AVDD_4_11") (pintype "power_in"))
      (node (ref "U4") (pin "15") (pinfunction "AVDD_5_15") (pintype "power_in"))
      (node (ref "U4") (pin "17") (pinfunction "AVDD_6_17") (pintype "power_in"))
      (node (ref "U4") (pin "21") (pinfunction "AVDD_21") (pintype "power_in"))
      (node (ref "U4") (pin "4") (pinfunction "AVDD_2_4") (pintype "power_in"))
      (node (ref "U4") (pin "8") (pinfunction "AVDD_3_8") (pintype "power_in"))
    )
    (net (code "64") (name "V5.0") (class "Default")
      (node (ref "C4") (pin "1") (pinfunction "1_1") (pintype "passive"))
      (node (ref "C5") (pin "2") (pinfunction "2_2") (pintype "passive"))
      (node (ref "U3") (pin "3") (pinfunction "OUT_3") (pintype "output"))
      (node (ref "U5") (pin "11") (pinfunction "VDD_11") (pintype "power_in"))
      (node (ref "U5") (pin "9") (pinfunction "BAT_9") (pintype "passive"))
    )
    (net (code "65") (name "VBAT") (class "Default")
      (node (ref "U1") (pin "1") (pinfunction "VBAT_1") (pintype "power_in"))
    )
    (net (code "66") (name "VDDA") (class "Default")
      (node (ref "U1") (pin "9") (pinfunction "VDDA_9") (pintype "power_in"))
    )
    (net (code "67") (name "VIN") (class "Default")
      (node (ref "C2") (pin "2") (pinfunction "2_2") (pintype "passive"))
      (node (ref "C3") (pin "1") (pinfunction "1_1") (pintype "passive"))
      (node (ref "U2") (pin "1") (pinfunction "VIN_1") (pintype "power_in"))
      (node (ref "U3") (pin "1") (pinfunction "IN_1") (pintype "input"))
    )
    (net (code "68") (name "VSSA") (class "Default")
      (node (ref "U1") (pin "8") (pinfunction "VSSA_8") (pintype "power_in"))
    )
    (net (code "69") (name "unconnected-(J1-Pad1)") (class "Default")
      (node (ref "J1") (pin "1") (pinfunction "1_1") (pintype "passive"))
    )
    (net (code "70") (name "unconnected-(J1-Pad2)") (class "Default")
      (node (ref "J1") (pin "2") (pinfunction "2_2") (pintype "passive"))
    )
    (net (code "71") (name "unconnected-(J1-Pad3)") (class "Default")
      (node (ref "J1") (pin "3") (pinfunction "3_3") (pintype "passive"))
    )
    (net (code "72") (name "unconnected-(J3-Pad7)") (class "Default")
      (node (ref "J3") (pin "7") (pinfunction "7_7") (pintype "bidirectional"))
    )
    (net (code "73") (name "unconnected-(SV1-Pad2)") (class "Default")
      (node (ref "SV1") (pin "2") (pinfunction "2_2") (pintype "passive"))
    )
    (net (code "74") (name "unconnected-(SV1-Pad4)") (class "Default")
      (node (ref "SV1") (pin "4") (pinfunction "4_4") (pintype "passive"))
    )
    (net (code "75") (name "unconnected-(SV1-Pad6)") (class "Default")
      (node (ref "SV1") (pin "6") (pinfunction "6_6") (pintype "passive"))
    )
    (net (code "76") (name "unconnected-(SV1-Pad8)") (class "Default")
      (node (ref "SV1") (pin "8") (pinfunction "8_8") (pintype "passive"))
    )
    (net (code "77") (name "unconnected-(SV1-Pad9)") (class "Default")
      (node (ref "SV1") (pin "9") (pinfunction "9_9") (pintype "passive"))
    )
    (net (code "78") (name "unconnected-(SV1-Pad10)") (class "Default")
      (node (ref "SV1") (pin "10") (pinfunction "10_10") (pintype "passive"))
    )
    (net (code "79") (name "unconnected-(U1A-PA1-Pad11)") (class "Default")
      (node (ref "U1") (pin "11") (pinfunction "PA1_11") (pintype "bidirectional"))
    )
    (net (code "80") (name "unconnected-(U1A-PA2-Pad12)") (class "Default")
      (node (ref "U1") (pin "12") (pinfunction "PA2_12") (pintype "bidirectional"))
    )
    (net (code "81") (name "unconnected-(U1A-PA3-Pad13)") (class "Default")
      (node (ref "U1") (pin "13") (pinfunction "PA3_13") (pintype "bidirectional"))
    )
    (net (code "82") (name "unconnected-(U1A-PA4-Pad14)") (class "Default")
      (node (ref "U1") (pin "14") (pinfunction "PA4_14") (pintype "bidirectional"))
    )
    (net (code "83") (name "unconnected-(U1A-PA8-Pad29)") (class "Default")
      (node (ref "U1") (pin "29") (pinfunction "PA8_29") (pintype "bidirectional"))
    )
    (net (code "84") (name "unconnected-(U1A-PA9-Pad30)") (class "Default")
      (node (ref "U1") (pin "30") (pinfunction "PA9_30") (pintype "bidirectional"))
    )
    (net (code "85") (name "unconnected-(U1A-PA10-Pad31)") (class "Default")
      (node (ref "U1") (pin "31") (pinfunction "PA10_31") (pintype "bidirectional"))
    )
    (net (code "86") (name "unconnected-(U1A-PA11-Pad32)") (class "Default")
      (node (ref "U1") (pin "32") (pinfunction "PA11_32") (pintype "bidirectional"))
    )
    (net (code "87") (name "unconnected-(U1A-PA12-Pad33)") (class "Default")
      (node (ref "U1") (pin "33") (pinfunction "PA12_33") (pintype "bidirectional"))
    )
    (net (code "88") (name "unconnected-(U1A-PB0-Pad18)") (class "Default")
      (node (ref "U1") (pin "18") (pinfunction "PB0_18") (pintype "bidirectional"))
    )
    (net (code "89") (name "unconnected-(U1A-PB1-Pad19)") (class "Default")
      (node (ref "U1") (pin "19") (pinfunction "PB1_19") (pintype "bidirectional"))
    )
    (net (code "90") (name "unconnected-(U1A-PB2-Pad20)") (class "Default")
      (node (ref "U1") (pin "20") (pinfunction "PB2_20") (pintype "bidirectional"))
    )
    (net (code "91") (name "unconnected-(U1A-PB11-Pad22)") (class "Default")
      (node (ref "U1") (pin "22") (pinfunction "PB11_22") (pintype "bidirectional"))
    )
    (net (code "92") (name "unconnected-(U1A-PB12-Pad25)") (class "Default")
      (node (ref "U1") (pin "25") (pinfunction "PB12_25") (pintype "bidirectional"))
    )
    (net (code "93") (name "unconnected-(U1A-PB13-Pad26)") (class "Default")
      (node (ref "U1") (pin "26") (pinfunction "PB13_26") (pintype "bidirectional"))
    )
    (net (code "94") (name "unconnected-(U1A-PB14-Pad27)") (class "Default")
      (node (ref "U1") (pin "27") (pinfunction "PB14_27") (pintype "bidirectional"))
    )
    (net (code "95") (name "unconnected-(U1A-PB15-Pad28)") (class "Default")
      (node (ref "U1") (pin "28") (pinfunction "PB15_28") (pintype "bidirectional"))
    )
    (net (code "96") (name "unconnected-(U1A-PC13-Pad2)") (class "Default")
      (node (ref "U1") (pin "2") (pinfunction "PC13_2") (pintype "bidirectional"))
    )
    (net (code "97") (name "unconnected-(U4-DNC-Pad7)") (class "Default")
      (node (ref "U4") (pin "7") (pinfunction "DNC_7") (pintype "no_connect"))
    )
    (net (code "98") (name "unconnected-(U4-DUPLED-Pad26)") (class "Default")
      (node (ref "U4") (pin "26") (pinfunction "DUPLED_26") (pintype "passive"))
    )
    (net (code "99") (name "unconnected-(U4-NC-Pad47)") (class "Default")
      (node (ref "U4") (pin "47") (pinfunction "NC_47") (pintype "no_connect"))
    )
    (net (code "100") (name "unconnected-(U4-NC_2-Pad12)") (class "Default")
      (node (ref "U4") (pin "12") (pinfunction "NC_2_12") (pintype "no_connect"))
    )
    (net (code "101") (name "unconnected-(U4-NC_3-Pad13)") (class "Default")
      (node (ref "U4") (pin "13") (pinfunction "NC_3_13") (pintype "no_connect"))
    )
    (net (code "102") (name "unconnected-(U4-NC_4-Pad46)") (class "Default")
      (node (ref "U4") (pin "46") (pinfunction "NC_4_46") (pintype "no_connect"))
    )
    (net (code "103") (name "unconnected-(U4-RSVD-Pad42)") (class "Default")
      (node (ref "U4") (pin "42") (pinfunction "RSVD_42") (pintype "passive"))
    )
    (net (code "104") (name "unconnected-(U4-RSVD_2-Pad23)") (class "Default")
      (node (ref "U4") (pin "23") (pinfunction "RSVD_2_23") (pintype "passive"))
    )
    (net (code "105") (name "unconnected-(U4-RSVD_3-Pad38)") (class "Default")
      (node (ref "U4") (pin "38") (pinfunction "RSVD_3_38") (pintype "passive"))
    )
    (net (code "106") (name "unconnected-(U4-RSVD_4-Pad39)") (class "Default")
      (node (ref "U4") (pin "39") (pinfunction "RSVD_4_39") (pintype "passive"))
    )
    (net (code "107") (name "unconnected-(U4-RSVD_5-Pad40)") (class "Default")
      (node (ref "U4") (pin "40") (pinfunction "RSVD_5_40") (pintype "passive"))
    )
    (net (code "108") (name "unconnected-(U4-RSVD_6-Pad41)") (class "Default")
      (node (ref "U4") (pin "41") (pinfunction "RSVD_6_41") (pintype "passive"))
    )
    (net (code "109") (name "unconnected-(U4-SCSN-Pad32)") (class "Default")
      (node (ref "U4") (pin "32") (pinfunction "SCSN_32") (pintype "passive"))
    )
    (net (code "110") (name "unconnected-(U4-SPDLED-Pad24)") (class "Default")
      (node (ref "U4") (pin "24") (pinfunction "SPDLED_24") (pintype "passive"))
    )
    (net (code "111") (name "unconnected-(U4-VBG-Pad18)") (class "Default")
      (node (ref "U4") (pin "18") (pinfunction "VBG_18") (pintype "passive"))
    )
    (net (code "112") (name "unconnected-(U5-RXI-Pad13)") (class "Default")
      (node (ref "U5") (pin "13") (pinfunction "RXI_13") (pintype "input"))
    )
    (net (code "113") (name "unconnected-(U5-TXI-Pad7)") (class "Default")
      (node (ref "U5") (pin "7") (pinfunction "TXI_7") (pintype "output"))
    )
    (net (code "114") (name "unconnected-(U5-VB-Pad2)") (class "Default")
      (node (ref "U5") (pin "2") (pinfunction "VB_2") (pintype "passive"))
    )
    (net (code "115") (name "unconnected-(U5-VS-Pad10)") (class "Default")
      (node (ref "U5") (pin "10") (pinfunction "VS_10") (pintype "passive"))
    )
  )
)
